# memory_card.net
KiCad netlist of a schematic drawn in EAGLE
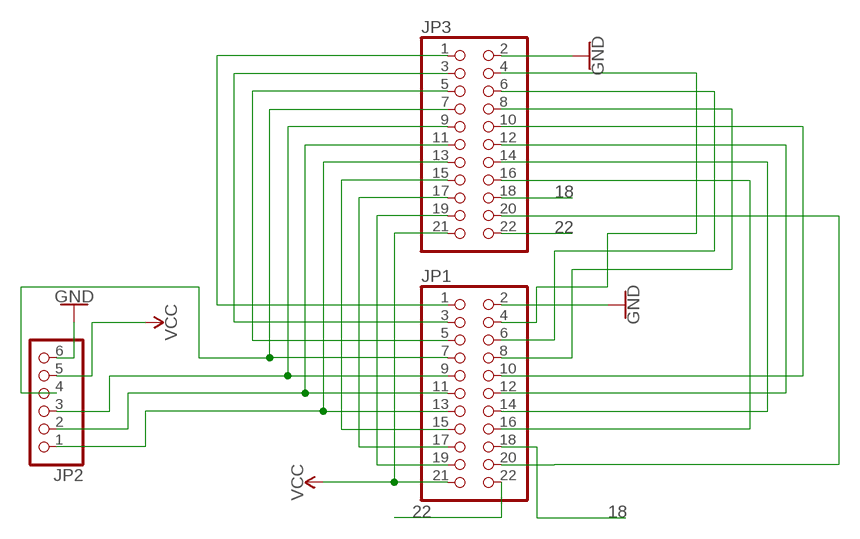
[diagram p0: schematic, sheet 1]

(export (version "E")
  (design (tool "Eeschema 10.0.6"))
  (components
    (comp (ref "JP1")
      (value "PINHD-2X11/90")
      (footprint "eagle-import:2X11_90")
      (libsource (lib "eagle-import") (part "PINHD-2X11/90"))
    )
    (comp (ref "JP2")
      (value "PINHD-1X6")
      (footprint "eagle-import:1X06")
      (libsource (lib "eagle-import") (part "PINHD-1X6"))
    )
    (comp (ref "JP3")
      (value "PINHD-2X11/90")
      (footprint "eagle-import:2X11_90")
      (libsource (lib "eagle-import") (part "PINHD-2X11/90"))
    )
  )
  (nets
    (net (code "1") (name "/18") (class "Default")
      (node (ref "JP1") (pin "18") (pinfunction "18_18") (pintype "passive"))
      (node (ref "JP3") (pin "18") (pinfunction "18_18") (pintype "passive"))
    )
    (net (code "2") (name "/22") (class "Default")
      (node (ref "JP1") (pin "22") (pinfunction "22_22") (pintype "passive"))
      (node (ref "JP3") (pin "22") (pinfunction "22_22") (pintype "passive"))
    )
    (net (code "3") (name "GND") (class "Default")
      (node (ref "JP1") (pin "2") (pinfunction "2_2") (pintype "passive"))
      (node (ref "JP2") (pin "6") (pinfunction "6_6") (pintype "passive"))
      (node (ref "JP3") (pin "2") (pinfunction "2_2") (pintype "passive"))
    )
    (net (code "4") (name "Net-(JP1-Pad1)") (class "Default")
      (node (ref "JP1") (pin "1") (pinfunction "1_1") (pintype "passive"))
      (node (ref "JP3") (pin "1") (pinfunction "1_1") (pintype "passive"))
    )
    (net (code "5") (name "Net-(JP1-Pad3)") (class "Default")
      (node (ref "JP1") (pin "3") (pinfunction "3_3") (pintype "passive"))
      (node (ref "JP3") (pin "3") (pinfunction "3_3") (pintype "passive"))
    )
    (net (code "6") (name "Net-(JP1-Pad4)") (class "Default")
      (node (ref "JP1") (pin "4") (pinfunction "4_4") (pintype "passive"))
      (node (ref "JP3") (pin "4") (pinfunction "4_4") (pintype "passive"))
    )
    (net (code "7") (name "Net-(JP1-Pad5)") (class "Default")
      (node (ref "JP1") (pin "5") (pinfunction "5_5") (pintype "passive"))
      (node (ref "JP3") (pin "5") (pinfunction "5_5") (pintype "passive"))
    )
    (net (code "8") (name "Net-(JP1-Pad6)") (class "Default")
      (node (ref "JP1") (pin "6") (pinfunction "6_6") (pintype "passive"))
      (node (ref "JP3") (pin "6") (pinfunction "6_6") (pintype "passive"))
    )
    (net (code "9") (name "Net-(JP1-Pad7)") (class "Default")
      (node (ref "JP1") (pin "7") (pinfunction "7_7") (pintype "passive"))
      (node (ref "JP2") (pin "4") (pinfunction "4_4") (pintype "passive"))
      (node (ref "JP3") (pin "7") (pinfunction "7_7") (pintype "passive"))
    )
    (net (code "10") (name "Net-(JP1-Pad8)") (class "Default")
      (node (ref "JP1") (pin "8") (pinfunction "8_8") (pintype "passive"))
      (node (ref "JP3") (pin "8") (pinfunction "8_8") (pintype "passive"))
    )
    (net (code "11") (name "Net-(JP1-Pad9)") (class "Default")
      (node (ref "JP1") (pin "9") (pinfunction "9_9") (pintype "passive"))
      (node (ref "JP2") (pin "3") (pinfunction "3_3") (pintype "passive"))
      (node (ref "JP3") (pin "9") (pinfunction "9_9") (pintype "passive"))
    )
    (net (code "12") (name "Net-(JP1-Pad10)") (class "Default")
      (node (ref "JP1") (pin "10") (pinfunction "10_10") (pintype "passive"))
      (node (ref "JP3") (pin "10") (pinfunction "10_10") (pintype "passive"))
    )
    (net (code "13") (name "Net-(JP1-Pad11)") (class "Default")
      (node (ref "JP1") (pin "11") (pinfunction "11_11") (pintype "passive"))
      (node (ref "JP2") (pin "2") (pinfunction "2_2") (pintype "passive"))
      (node (ref "JP3") (pin "11") (pinfunction "11_11") (pintype "passive"))
    )
    (net (code "14") (name "Net-(JP1-Pad12)") (class "Default")
      (node (ref "JP1") (pin "12") (pinfunction "12_12") (pintype "passive"))
      (node (ref "JP3") (pin "12") (pinfunction "12_12") (pintype "passive"))
    )
    (net (code "15") (name "Net-(JP1-Pad13)") (class "Default")
      (node (ref "JP1") (pin "13") (pinfunction "13_13") (pintype "passive"))
      (node (ref "JP2") (pin "1") (pinfunction "1_1") (pintype "passive"))
      (node (ref "JP3") (pin "13") (pinfunction "13_13") (pintype "passive"))
    )
    (net (code "16") (name "Net-(JP1-Pad14)") (class "Default")
      (node (ref "JP1") (pin "14") (pinfunction "14_14") (pintype "passive"))
      (node (ref "JP3") (pin "14") (pinfunction "14_14") (pintype "passive"))
    )
    (net (code "17") (name "Net-(JP1-Pad15)") (class "Default")
      (node (ref "JP1") (pin "15") (pinfunction "15_15") (pintype "passive"))
      (node (ref "JP3") (pin "15") (pinfunction "15_15") (pintype "passive"))
    )
    (net (code "18") (name "Net-(JP1-Pad16)") (class "Default")
      (node (ref "JP1") (pin "16") (pinfunction "16_16") (pintype "passive"))
      (node (ref "JP3") (pin "16") (pinfunction "16_16") (pintype "passive"))
    )
    (net (code "19") (name "Net-(JP1-Pad17)") (class "Default")
      (node (ref "JP1") (pin "17") (pinfunction "17_17") (pintype "passive"))
      (node (ref "JP3") (pin "17") (pinfunction "17_17") (pintype "passive"))
    )
    (net (code "20") (name "Net-(JP1-Pad19)") (class "Default")
      (node (ref "JP1") (pin "19") (pinfunction "19_19") (pintype "passive"))
      (node (ref "JP3") (pin "19") (pinfunction "19_19") (pintype "passive"))
    )
    (net (code "21") (name "Net-(JP1-Pad20)") (class "Default")
      (node (ref "JP1") (pin "20") (pinfunction "20_20") (pintype "passive"))
      (node (ref "JP3") (pin "20") (pinfunction "20_20") (pintype "passive"))
    )
    (net (code "22") (name "VCC") (class "Default")
      (node (ref "JP1") (pin "21") (pinfunction "21_21") (pintype "passive"))
      (node (ref "JP2") (pin "5") (pinfunction "5_5") (pintype "passive"))
      (node (ref "JP3") (pin "21") (pinfunction "21_21") (pintype "passive"))
    )
  )
)
